# 07_CAN.net
KiCad netlist of a schematic drawn in Altium Designer
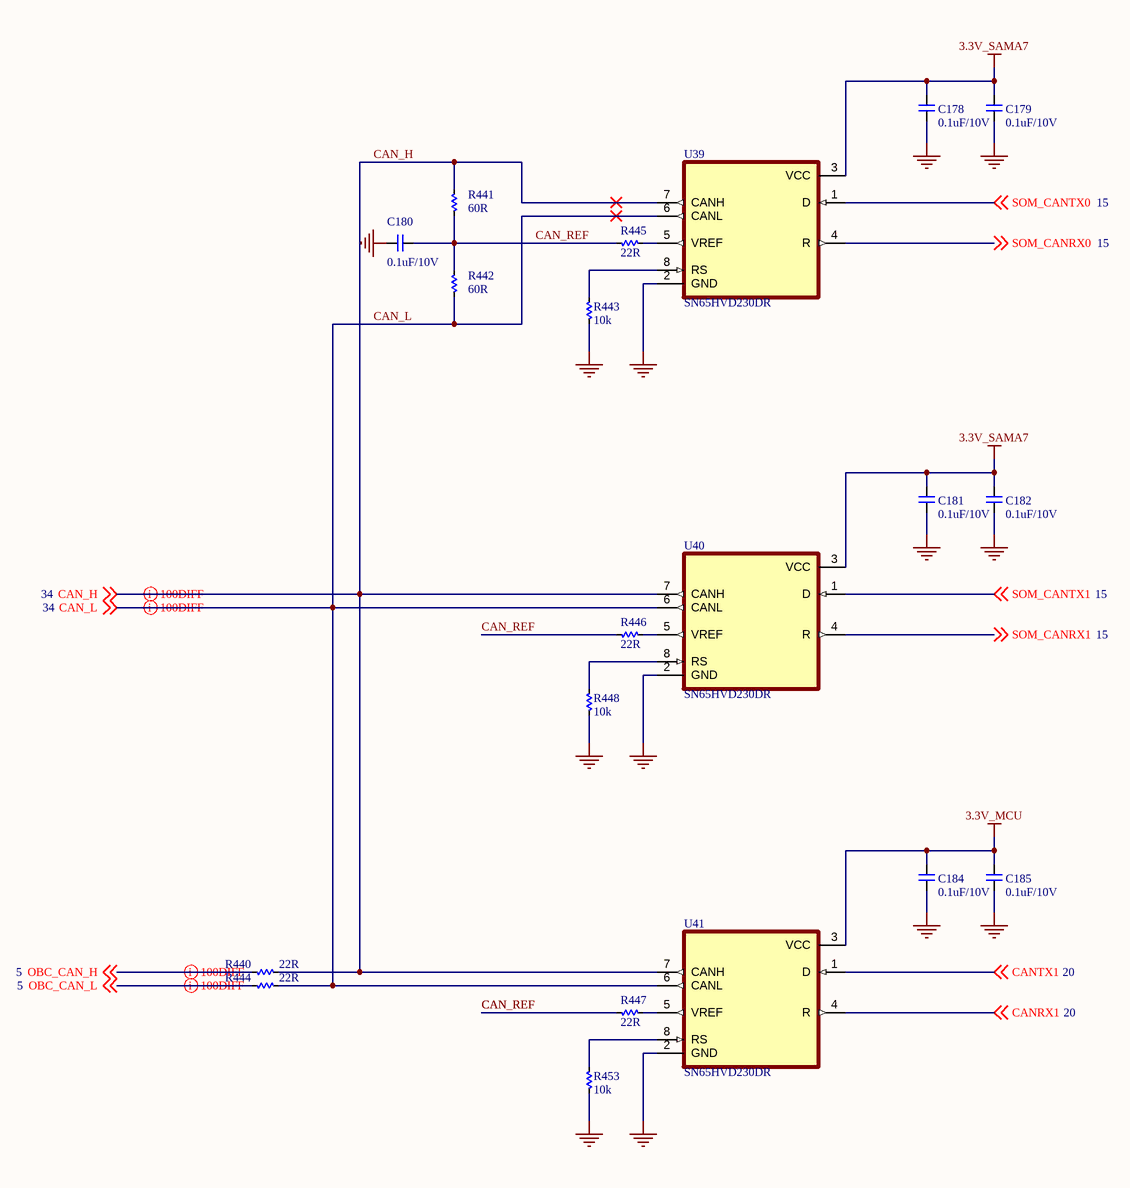
[diagram p0: 07_CAN.SchDoc]

(export (version "E")
  (design (tool "Eeschema 10.0.6"))
  (components
    (comp (ref "C178")
      (value "0.1uF/10V")
      (footprint "CAP_C_1005X60")
      (description "CAP")
      (libsource (lib "LABLIB") (part "_CAP_C_2"))
    )
    (comp (ref "C179")
      (value "0.1uF/10V")
      (footprint "CAP_C_1005X60")
      (description "CAP")
      (libsource (lib "LABLIB") (part "_CAP_C_2"))
    )
    (comp (ref "C180")
      (value "0.1uF/10V")
      (footprint "CAP_C_1005X60")
      (description "CAP")
      (libsource (lib "LABLIB") (part "_CAP_C_2"))
    )
    (comp (ref "C181")
      (value "0.1uF/10V")
      (footprint "CAP_C_1005X60")
      (description "CAP")
      (libsource (lib "LABLIB") (part "_CAP_C_2"))
    )
    (comp (ref "C182")
      (value "0.1uF/10V")
      (footprint "CAP_C_1005X60")
      (description "CAP")
      (libsource (lib "LABLIB") (part "_CAP_C_2"))
    )
    (comp (ref "C184")
      (value "0.1uF/10V")
      (footprint "CAP_C_1005X60")
      (description "CAP")
      (libsource (lib "LABLIB") (part "_CAP_C_2"))
    )
    (comp (ref "C185")
      (value "0.1uF/10V")
      (footprint "CAP_C_1005X60")
      (description "CAP")
      (libsource (lib "LABLIB") (part "_CAP_C_2"))
    )
    (comp (ref "R440")
      (value "22R")
      (footprint "RES_C_1005X40")
      (description "RES")
      (libsource (lib "LABLIB") (part "_RES_B_2"))
    )
    (comp (ref "R441")
      (value "60R")
      (footprint "RES_C_1005X40")
      (description "RES")
      (libsource (lib "LABLIB") (part "_RES_B_2"))
    )
    (comp (ref "R442")
      (value "60R")
      (footprint "RES_C_1005X40")
      (description "RES")
      (libsource (lib "LABLIB") (part "_RES_B_2"))
    )
    (comp (ref "R443")
      (value "10k")
      (footprint "RES_C_1005X40")
      (description "RES")
      (libsource (lib "LABLIB") (part "_RES_B_2"))
    )
    (comp (ref "R444")
      (value "22R")
      (footprint "RES_C_1005X40")
      (description "RES")
      (libsource (lib "LABLIB") (part "_RES_B_2"))
    )
    (comp (ref "R445")
      (value "22R")
      (footprint "RES_C_1005X40")
      (description "RES")
      (libsource (lib "LABLIB") (part "_RES_B_2"))
    )
    (comp (ref "R446")
      (value "22R")
      (footprint "RES_C_1005X40")
      (description "RES")
      (libsource (lib "LABLIB") (part "_RES_B_2"))
    )
    (comp (ref "R447")
      (value "22R")
      (footprint "RES_C_1005X40")
      (description "RES")
      (libsource (lib "LABLIB") (part "_RES_B_2"))
    )
    (comp (ref "R448")
      (value "10k")
      (footprint "RES_C_1005X40")
      (description "RES")
      (libsource (lib "LABLIB") (part "_RES_B_2"))
    )
    (comp (ref "R453")
      (value "10k")
      (footprint "RES_C_1005X40")
      (description "RES")
      (libsource (lib "LABLIB") (part "_RES_B_2"))
    )
    (comp (ref "U39")
      (value "SN65HVD230DR")
      (footprint "SOIC127P599X175-8N")
      (description "3.3 V CAN Transceiver with Standby Mode")
      (fields (field (name "MF") "Texas Instruments"))
      (libsource (lib "COMM_SCHLIB") (part "SN65HVD230DR"))
    )
    (comp (ref "U40")
      (value "SN65HVD230DR")
      (footprint "SOIC127P599X175-8N")
      (description "3.3 V CAN Transceiver with Standby Mode")
      (fields (field (name "MF") "Texas Instruments"))
      (libsource (lib "COMM_SCHLIB") (part "SN65HVD230DR"))
    )
    (comp (ref "U41")
      (value "SN65HVD230DR")
      (footprint "SOIC127P599X175-8N")
      (description "3.3 V CAN Transceiver with Standby Mode")
      (fields (field (name "MF") "Texas Instruments"))
      (libsource (lib "COMM_SCHLIB") (part "SN65HVD230DR"))
    )
  )
  (nets
    (net (code "1") (name "/CAN_REF") (class "Default")
      (node (ref "C180") (pin "1") (pinfunction "1_1") (pintype "passive"))
      (node (ref "R441") (pin "1") (pinfunction "1_1") (pintype "passive"))
      (node (ref "R442") (pin "2") (pinfunction "2_2") (pintype "passive"))
      (node (ref "R445") (pin "1") (pinfunction "1_1") (pintype "passive"))
      (node (ref "R446") (pin "1") (pinfunction "1_1") (pintype "passive"))
      (node (ref "R447") (pin "1") (pinfunction "1_1") (pintype "passive"))
    )
    (net (code "2") (name "3.3V_MCU") (class "Default")
      (node (ref "C184") (pin "1") (pinfunction "1_1") (pintype "passive"))
      (node (ref "C185") (pin "1") (pinfunction "1_1") (pintype "passive"))
      (node (ref "U41") (pin "3") (pinfunction "VCC_3") (pintype "power_in"))
    )
    (net (code "3") (name "3.3V_SAMA7") (class "Default")
      (node (ref "C178") (pin "1") (pinfunction "1_1") (pintype "passive"))
      (node (ref "C179") (pin "1") (pinfunction "1_1") (pintype "passive"))
      (node (ref "C181") (pin "1") (pinfunction "1_1") (pintype "passive"))
      (node (ref "C182") (pin "1") (pinfunction "1_1") (pintype "passive"))
      (node (ref "U39") (pin "3") (pinfunction "VCC_3") (pintype "power_in"))
      (node (ref "U40") (pin "3") (pinfunction "VCC_3") (pintype "power_in"))
    )
    (net (code "4") (name "CANRX1") (class "Default")
      (node (ref "U41") (pin "4") (pinfunction "R_4") (pintype "output"))
    )
    (net (code "5") (name "CANTX1") (class "Default")
      (node (ref "U41") (pin "1") (pinfunction "D_1") (pintype "input"))
    )
    (net (code "6") (name "CAN_H") (class "Default")
      (node (ref "R440") (pin "2") (pinfunction "2_2") (pintype "passive"))
      (node (ref "R441") (pin "2") (pinfunction "2_2") (pintype "passive"))
      (node (ref "U39") (pin "7") (pinfunction "CANH_7") (pintype "output"))
      (node (ref "U40") (pin "7") (pinfunction "CANH_7") (pintype "output"))
      (node (ref "U41") (pin "7") (pinfunction "CANH_7") (pintype "output"))
    )
    (net (code "7") (name "CAN_L") (class "Default")
      (node (ref "R442") (pin "1") (pinfunction "1_1") (pintype "passive"))
      (node (ref "R444") (pin "2") (pinfunction "2_2") (pintype "passive"))
      (node (ref "U39") (pin "6") (pinfunction "CANL_6") (pintype "output"))
      (node (ref "U40") (pin "6") (pinfunction "CANL_6") (pintype "output"))
      (node (ref "U41") (pin "6") (pinfunction "CANL_6") (pintype "output"))
    )
    (net (code "8") (name "GND") (class "Default")
      (node (ref "C178") (pin "2") (pinfunction "2_2") (pintype "passive"))
      (node (ref "C179") (pin "2") (pinfunction "2_2") (pintype "passive"))
      (node (ref "C180") (pin "2") (pinfunction "2_2") (pintype "passive"))
      (node (ref "C181") (pin "2") (pinfunction "2_2") (pintype "passive"))
      (node (ref "C182") (pin "2") (pinfunction "2_2") (pintype "passive"))
      (node (ref "C184") (pin "2") (pinfunction "2_2") (pintype "passive"))
      (node (ref "C185") (pin "2") (pinfunction "2_2") (pintype "passive"))
      (node (ref "R443") (pin "1") (pinfunction "1_1") (pintype "passive"))
      (node (ref "R448") (pin "1") (pinfunction "1_1") (pintype "passive"))
      (node (ref "R453") (pin "1") (pinfunction "1_1") (pintype "passive"))
      (node (ref "U39") (pin "2") (pinfunction "GND_2") (pintype "power_in"))
      (node (ref "U40") (pin "2") (pinfunction "GND_2") (pintype "power_in"))
      (node (ref "U41") (pin "2") (pinfunction "GND_2") (pintype "power_in"))
    )
    (net (code "9") (name "Net-(U39-RS)") (class "Default")
      (node (ref "R443") (pin "2") (pinfunction "2_2") (pintype "passive"))
      (node (ref "U39") (pin "8") (pinfunction "RS_8") (pintype "input"))
    )
    (net (code "10") (name "Net-(U39-VREF)") (class "Default")
      (node (ref "R445") (pin "2") (pinfunction "2_2") (pintype "passive"))
      (node (ref "U39") (pin "5") (pinfunction "VREF_5") (pintype "output"))
    )
    (net (code "11") (name "Net-(U40-RS)") (class "Default")
      (node (ref "R448") (pin "2") (pinfunction "2_2") (pintype "passive"))
      (node (ref "U40") (pin "8") (pinfunction "RS_8") (pintype "input"))
    )
    (net (code "12") (name "Net-(U40-VREF)") (class "Default")
      (node (ref "R446") (pin "2") (pinfunction "2_2") (pintype "passive"))
      (node (ref "U40") (pin "5") (pinfunction "VREF_5") (pintype "output"))
    )
    (net (code "13") (name "Net-(U41-RS)") (class "Default")
      (node (ref "R453") (pin "2") (pinfunction "2_2") (pintype "passive"))
      (node (ref "U41") (pin "8") (pinfunction "RS_8") (pintype "input"))
    )
    (net (code "14") (name "Net-(U41-VREF)") (class "Default")
      (node (ref "R447") (pin "2") (pinfunction "2_2") (pintype "passive"))
      (node (ref "U41") (pin "5") (pinfunction "VREF_5") (pintype "output"))
    )
    (net (code "15") (name "OBC_CAN_H") (class "Default")
      (node (ref "R440") (pin "1") (pinfunction "1_1") (pintype "passive"))
    )
    (net (code "16") (name "OBC_CAN_L") (class "Default")
      (node (ref "R444") (pin "1") (pinfunction "1_1") (pintype "passive"))
    )
    (net (code "17") (name "SOM_CANRX0") (class "Default")
      (node (ref "U39") (pin "4") (pinfunction "R_4") (pintype "output"))
    )
    (net (code "18") (name "SOM_CANRX1") (class "Default")
      (node (ref "U40") (pin "4") (pinfunction "R_4") (pintype "output"))
    )
    (net (code "19") (name "SOM_CANTX0") (class "Default")
      (node (ref "U39") (pin "1") (pinfunction "D_1") (pintype "input"))
    )
    (net (code "20") (name "SOM_CANTX1") (class "Default")
      (node (ref "U40") (pin "1") (pinfunction "D_1") (pintype "input"))
    )
  )
)
